# SparkFun_dToF-TMF8821_Mini.net
KiCad netlist of a schematic drawn in EAGLE
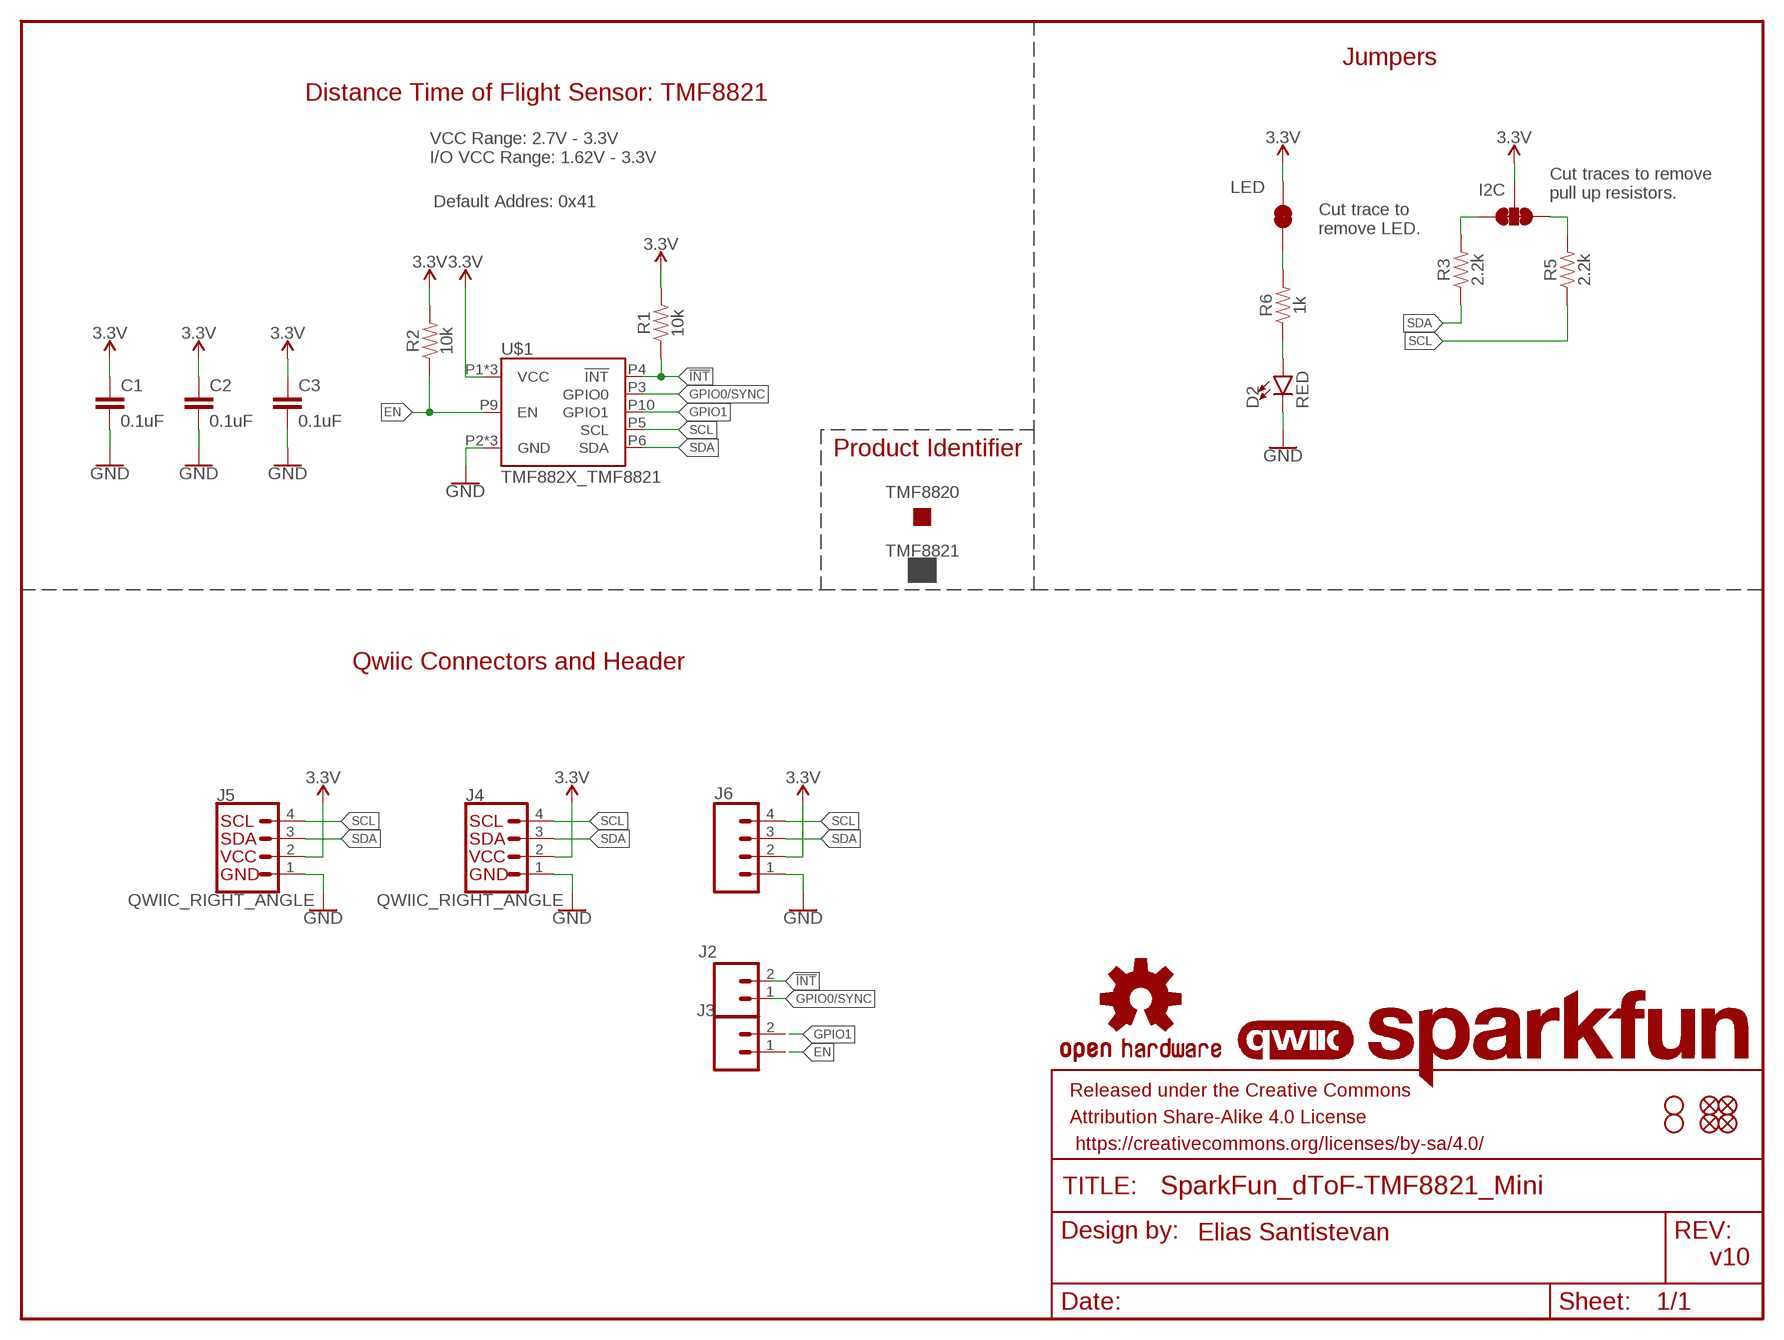
[diagram p0: schematic, sheet 1]

(export (version "E")
  (design (tool "Eeschema 10.0.6"))
  (components
    (comp (ref "C1")
      (value "0.1uF")
      (footprint "eagle-import:0402-TIGHT")
      (libsource (lib "eagle-import") (part "0.1UF-0402T-6.3V-10%-X7R"))
    )
    (comp (ref "C2")
      (value "0.1uF")
      (footprint "eagle-import:0402-TIGHT")
      (libsource (lib "eagle-import") (part "0.1UF-0402T-6.3V-10%-X7R"))
    )
    (comp (ref "C3")
      (value "0.1uF")
      (footprint "eagle-import:0402-TIGHT")
      (libsource (lib "eagle-import") (part "0.1UF-0402T-6.3V-10%-X7R"))
    )
    (comp (ref "D2")
      (value "RED")
      (footprint "eagle-import:LED-0603")
      (libsource (lib "eagle-import") (part "LED-RED0603"))
    )
    (comp (ref "FD5")
      (value "FIDUCIALUFIDUCIAL")
      (footprint "eagle-import:FIDUCIAL-MICRO")
      (libsource (lib "eagle-import") (part "FIDUCIALUFIDUCIAL"))
    )
    (comp (ref "FD6")
      (value "FIDUCIALUFIDUCIAL")
      (footprint "eagle-import:FIDUCIAL-MICRO")
      (libsource (lib "eagle-import") (part "FIDUCIALUFIDUCIAL"))
    )
    (comp (ref "FD7")
      (value "FIDUCIALUFIDUCIAL")
      (footprint "eagle-import:FIDUCIAL-MICRO")
      (libsource (lib "eagle-import") (part "FIDUCIALUFIDUCIAL"))
    )
    (comp (ref "FD8")
      (value "FIDUCIALUFIDUCIAL")
      (footprint "eagle-import:FIDUCIAL-MICRO")
      (libsource (lib "eagle-import") (part "FIDUCIALUFIDUCIAL"))
    )
    (comp (ref "FRAME2")
      (value "FRAME-LETTER")
      (footprint "eagle-import:CREATIVE_COMMONS")
      (libsource (lib "eagle-import") (part "FRAME-LETTER"))
    )
    (comp (ref "H7")
      (value "STAND-OFFTIGHT")
      (footprint "eagle-import:STAND-OFF-TIGHT")
      (libsource (lib "eagle-import") (part "STAND-OFFTIGHT"))
    )
    (comp (ref "H8")
      (value "STAND-OFFTIGHT")
      (footprint "eagle-import:STAND-OFF-TIGHT")
      (libsource (lib "eagle-import") (part "STAND-OFFTIGHT"))
    )
    (comp (ref "I2C")
      (value "I2C_PU")
      (footprint "eagle-import:SMT-JUMPER_3_2-NC_TRACE_SILK")
      (libsource (lib "eagle-import") (part "JUMPER-SMT_3_2-NC_TRACE_SILK"))
    )
    (comp (ref "J2")
      (value "CONN_021X02_NO_SILK")
      (footprint "eagle-import:1X02_NO_SILK")
      (libsource (lib "eagle-import") (part "CONN_021X02_NO_SILK"))
    )
    (comp (ref "J3")
      (value "CONN_021X02_NO_SILK")
      (footprint "eagle-import:1X02_NO_SILK")
      (libsource (lib "eagle-import") (part "CONN_021X02_NO_SILK"))
    )
    (comp (ref "J4")
      (value "QWIIC_RIGHT_ANGLE")
      (footprint "eagle-import:JST04_1MM_RA")
      (libsource (lib "eagle-import") (part "QWIIC_CONNECTORJS-1MM"))
    )
    (comp (ref "J5")
      (value "QWIIC_RIGHT_ANGLE")
      (footprint "eagle-import:JST04_1MM_RA")
      (libsource (lib "eagle-import") (part "QWIIC_CONNECTORJS-1MM"))
    )
    (comp (ref "J6")
      (value "CONN_041X04_NO_SILK")
      (footprint "eagle-import:1X04_NO_SILK")
      (libsource (lib "eagle-import") (part "CONN_041X04_NO_SILK"))
    )
    (comp (ref "LED")
      (value "LED")
      (footprint "eagle-import:SMT-JUMPER_2_NC_TRACE_SILK")
      (libsource (lib "eagle-import") (part "JUMPER-SMT_2_NC_TRACE_SILK"))
    )
    (comp (ref "LOGO1")
      (value "SFE_LOGO_NAMEBLANK")
      (footprint "eagle-import:BLANK")
      (libsource (lib "eagle-import") (part "SFE_LOGO_NAMEBLANK"))
    )
    (comp (ref "LOGO2")
      (value "QWIIC_LOGO_4MM")
      (footprint "eagle-import:QWIIC_4MM")
      (libsource (lib "eagle-import") (part "QWIIC_LOGO_4MM"))
    )
    (comp (ref "LOGO3")
      (value "OSHW-LOGONO_SILK")
      (footprint "eagle-import:DUMMY")
      (libsource (lib "eagle-import") (part "OSHW-LOGONO_SILK"))
    )
    (comp (ref "R1")
      (value "10k")
      (footprint "eagle-import:0402-TIGHT")
      (libsource (lib "eagle-import") (part "10KOHM-0402T-1/16W-1%"))
    )
    (comp (ref "R2")
      (value "10k")
      (footprint "eagle-import:0402-TIGHT")
      (libsource (lib "eagle-import") (part "10KOHM-0402T-1/16W-1%"))
    )
    (comp (ref "R3")
      (value "2.2k")
      (footprint "eagle-import:0402-TIGHT")
      (libsource (lib "eagle-import") (part "2.2KOHM-0402T-1/16W-1%"))
    )
    (comp (ref "R5")
      (value "2.2k")
      (footprint "eagle-import:0402-TIGHT")
      (libsource (lib "eagle-import") (part "2.2KOHM-0402T-1/16W-1%"))
    )
    (comp (ref "R6")
      (value "1k")
      (footprint "eagle-import:0402-TIGHT")
      (libsource (lib "eagle-import") (part "1KOHM-0402T-1/16W-1%"))
    )
    (comp (ref "TMF8820")
      (value "PROD_ID_NO-PASTE_SILK")
      (footprint "eagle-import:PRODUCT_IDENT_NO_SILK")
      (libsource (lib "eagle-import") (part "PROD_ID_NO-PASTE_SILK"))
    )
    (comp (ref "TMF8821")
      (value "PROD_ID_PASTE_SILK")
      (footprint "eagle-import:PRODUCT_IDENT_PASTE_SILK")
      (libsource (lib "eagle-import") (part "PROD_ID_PASTE_SILK"))
    )
    (comp (ref "U$1")
      (value "TMF882X_TMF8821")
      (footprint "eagle-import:TMF882X")
      (libsource (lib "eagle-import") (part "TMF882X_TMF8821"))
    )
  )
  (nets
    (net (code "1") (name "/~{INT}") (class "Default")
      (node (ref "J2") (pin "2") (pinfunction "2_2") (pintype "passive"))
      (node (ref "R1") (pin "1") (pinfunction "1_1") (pintype "passive"))
      (node (ref "U$1") (pin "P4") (pinfunction "~{INT}_P4") (pintype "bidirectional"))
    )
    (net (code "2") (name "3.3V") (class "Default")
      (node (ref "C1") (pin "1") (pinfunction "1_1") (pintype "passive"))
      (node (ref "C2") (pin "1") (pinfunction "1_1") (pintype "passive"))
      (node (ref "C3") (pin "1") (pinfunction "1_1") (pintype "passive"))
      (node (ref "I2C") (pin "2") (pinfunction "2_2") (pintype "passive"))
      (node (ref "J4") (pin "2") (pinfunction "2_2") (pintype "power_in"))
      (node (ref "J5") (pin "2") (pinfunction "2_2") (pintype "power_in"))
      (node (ref "J6") (pin "2") (pinfunction "2_2") (pintype "passive"))
      (node (ref "LED") (pin "2") (pinfunction "2_2") (pintype "passive"))
      (node (ref "R1") (pin "2") (pinfunction "2_2") (pintype "passive"))
      (node (ref "R2") (pin "2") (pinfunction "2_2") (pintype "passive"))
      (node (ref "U$1") (pin "P1") (pinfunction "VCC_P1") (pintype "power_in"))
      (node (ref "U$1") (pin "P12") (pinfunction "VCC_P12") (pintype "power_in"))
      (node (ref "U$1") (pin "P7") (pinfunction "VCC_P7") (pintype "power_in"))
    )
    (net (code "3") (name "EN") (class "Default")
      (node (ref "J3") (pin "1") (pinfunction "1_1") (pintype "passive"))
      (node (ref "R2") (pin "1") (pinfunction "1_1") (pintype "passive"))
      (node (ref "U$1") (pin "P9") (pinfunction "EN_P9") (pintype "input"))
    )
    (net (code "4") (name "GND") (class "Default")
      (node (ref "C1") (pin "2") (pinfunction "2_2") (pintype "passive"))
      (node (ref "C2") (pin "2") (pinfunction "2_2") (pintype "passive"))
      (node (ref "C3") (pin "2") (pinfunction "2_2") (pintype "passive"))
      (node (ref "D2") (pin "C") (pinfunction "C_C") (pintype "passive"))
      (node (ref "J4") (pin "1") (pinfunction "1_1") (pintype "power_in"))
      (node (ref "J5") (pin "1") (pinfunction "1_1") (pintype "power_in"))
      (node (ref "J6") (pin "1") (pinfunction "1_1") (pintype "passive"))
      (node (ref "U$1") (pin "P11") (pinfunction "GND_P11") (pintype "power_in"))
      (node (ref "U$1") (pin "P2") (pinfunction "GND_P2") (pintype "power_in"))
      (node (ref "U$1") (pin "P8") (pinfunction "GND_P8") (pintype "power_in"))
    )
    (net (code "5") (name "GPIO0{slash}SYNC") (class "Default")
      (node (ref "J2") (pin "1") (pinfunction "1_1") (pintype "passive"))
      (node (ref "U$1") (pin "P3") (pinfunction "GPIO0_P3") (pintype "bidirectional"))
    )
    (net (code "6") (name "GPIO1") (class "Default")
      (node (ref "J3") (pin "2") (pinfunction "2_2") (pintype "passive"))
      (node (ref "U$1") (pin "P10") (pinfunction "GPIO1_P10") (pintype "bidirectional"))
    )
    (net (code "7") (name "Net-(D2-PadA)") (class "Default")
      (node (ref "D2") (pin "A") (pinfunction "A_A") (pintype "passive"))
      (node (ref "R6") (pin "1") (pinfunction "1_1") (pintype "passive"))
    )
    (net (code "8") (name "Net-(I2C-Pad1)") (class "Default")
      (node (ref "I2C") (pin "1") (pinfunction "1_1") (pintype "passive"))
      (node (ref "R5") (pin "2") (pinfunction "2_2") (pintype "passive"))
    )
    (net (code "9") (name "Net-(I2C-Pad3)") (class "Default")
      (node (ref "I2C") (pin "3") (pinfunction "3_3") (pintype "passive"))
      (node (ref "R3") (pin "2") (pinfunction "2_2") (pintype "passive"))
    )
    (net (code "10") (name "Net-(LED-Pad1)") (class "Default")
      (node (ref "LED") (pin "1") (pinfunction "1_1") (pintype "passive"))
      (node (ref "R6") (pin "2") (pinfunction "2_2") (pintype "passive"))
    )
    (net (code "11") (name "SCL") (class "Default")
      (node (ref "J4") (pin "4") (pinfunction "4_4") (pintype "passive"))
      (node (ref "J5") (pin "4") (pinfunction "4_4") (pintype "passive"))
      (node (ref "J6") (pin "4") (pinfunction "4_4") (pintype "passive"))
      (node (ref "R5") (pin "1") (pinfunction "1_1") (pintype "passive"))
      (node (ref "U$1") (pin "P5") (pinfunction "SCL_P5") (pintype "bidirectional"))
    )
    (net (code "12") (name "SDA") (class "Default")
      (node (ref "J4") (pin "3") (pinfunction "3_3") (pintype "passive"))
      (node (ref "J5") (pin "3") (pinfunction "3_3") (pintype "passive"))
      (node (ref "J6") (pin "3") (pinfunction "3_3") (pintype "passive"))
      (node (ref "R3") (pin "1") (pinfunction "1_1") (pintype "passive"))
      (node (ref "U$1") (pin "P6") (pinfunction "SDA_P6") (pintype "bidirectional"))
    )
  )
)
